# DisplayLCD-RS485.net
KiCad netlist of a schematic drawn in Altium Designer
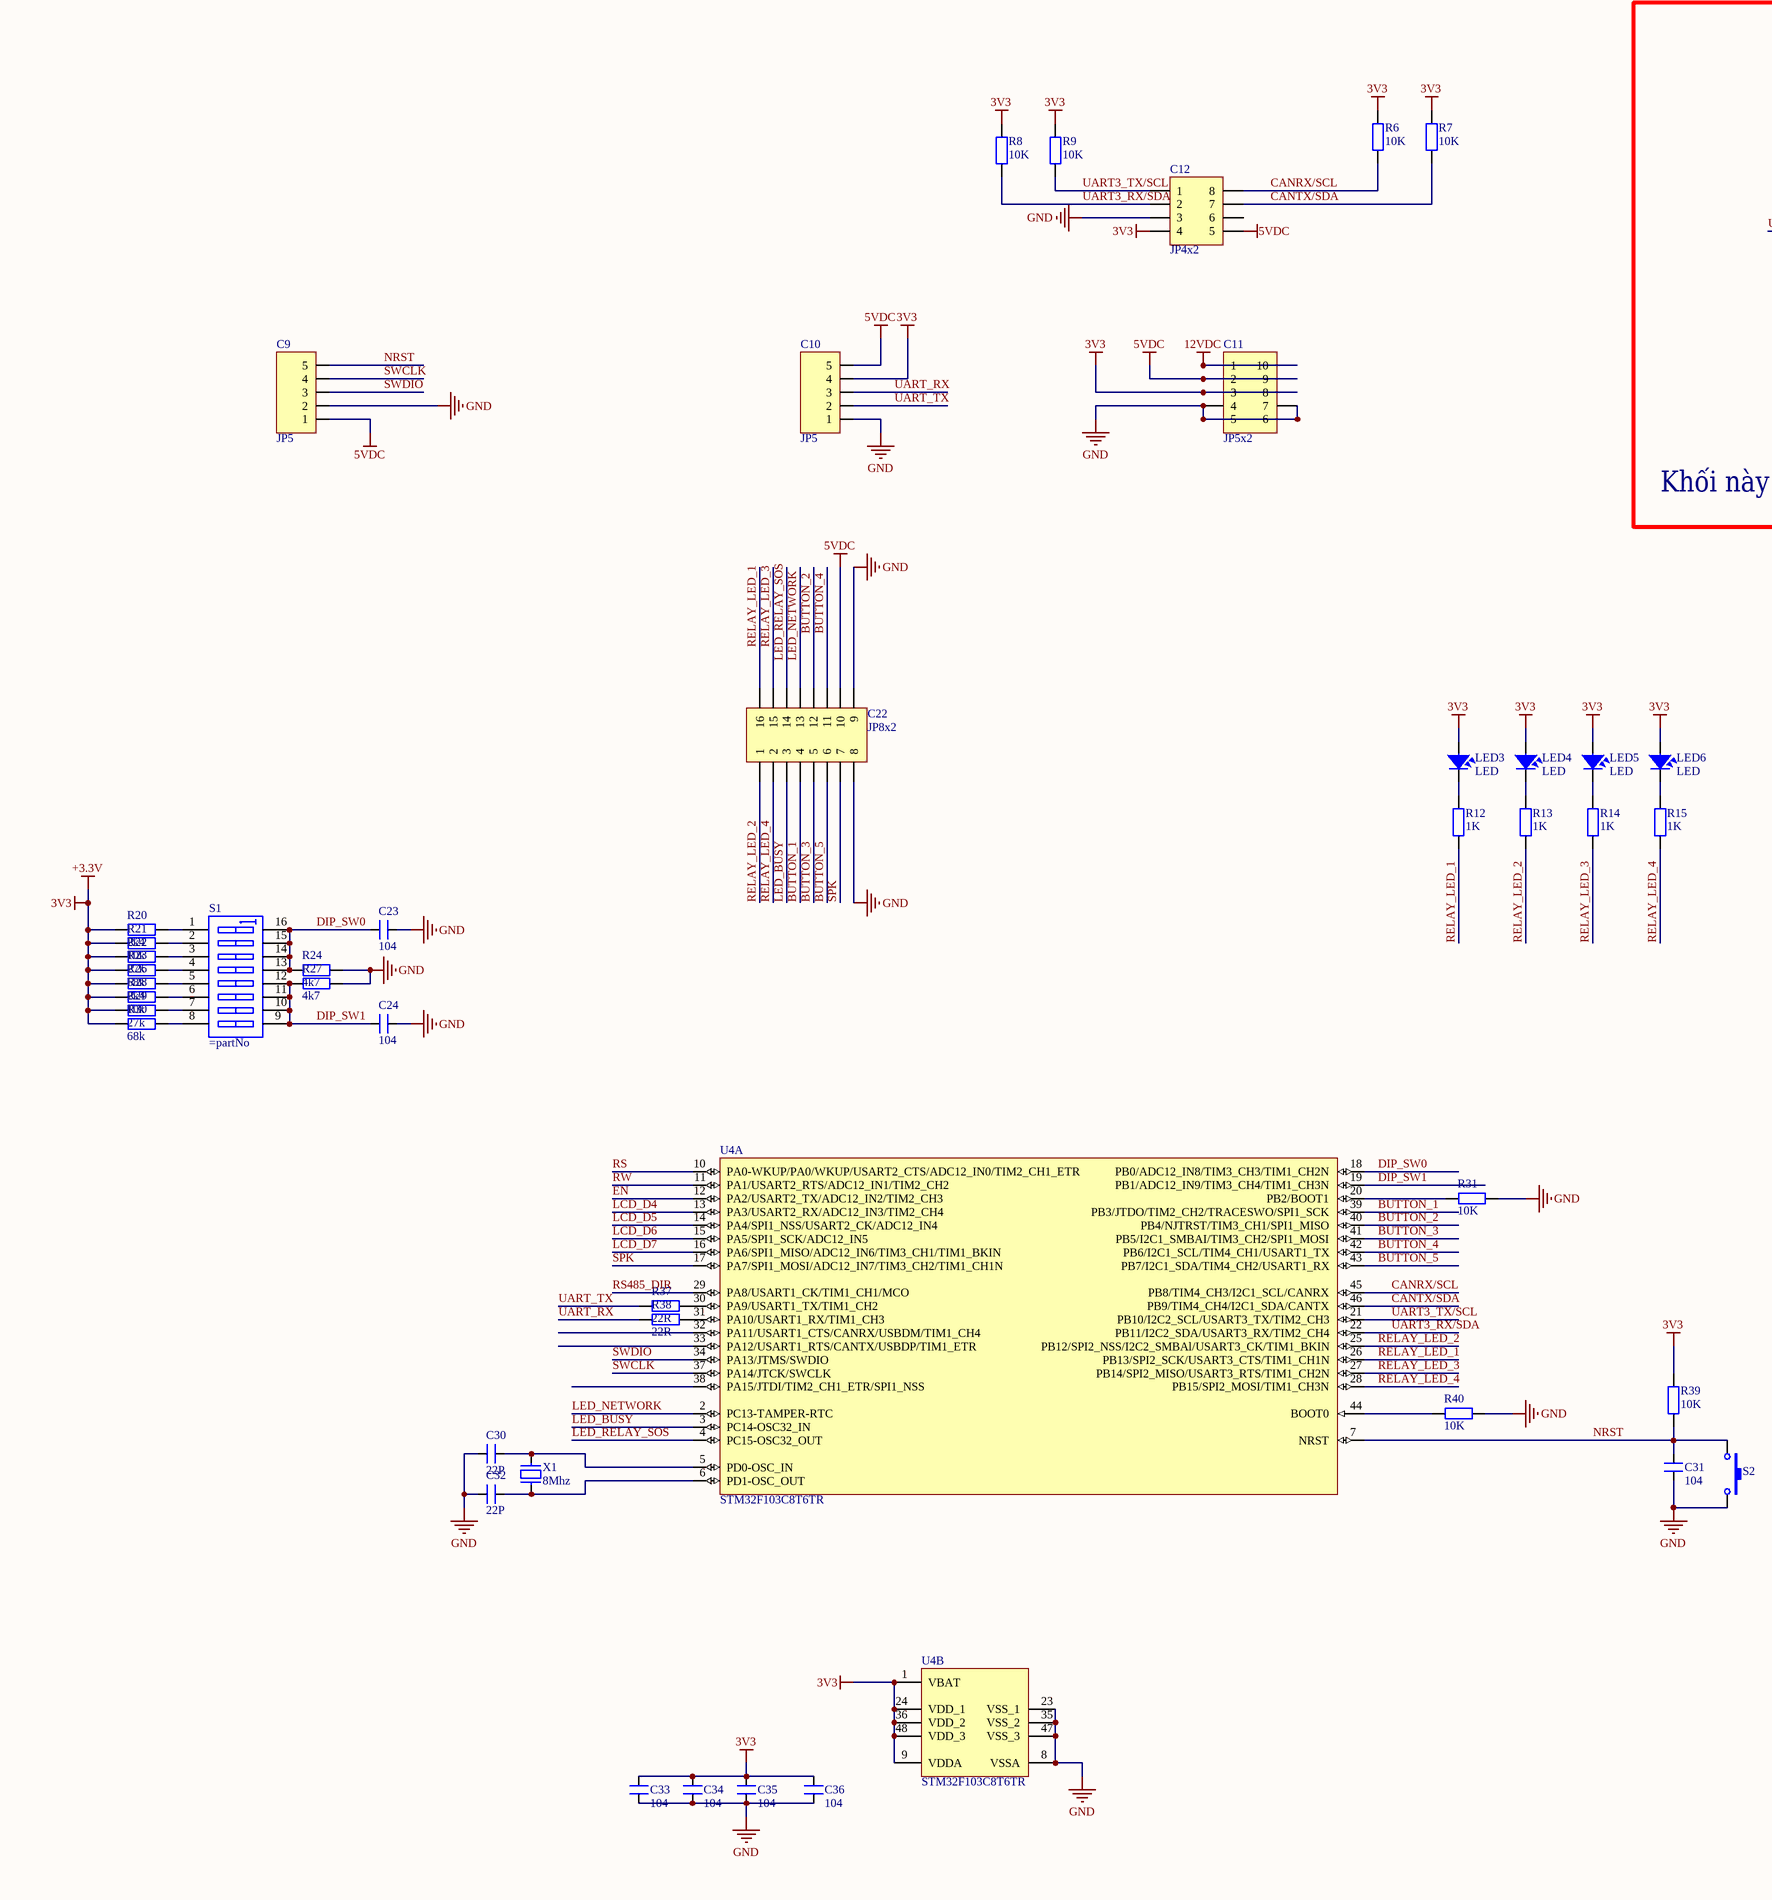
[diagram p0: DisplayLCD-RS485.SchDoc, left]
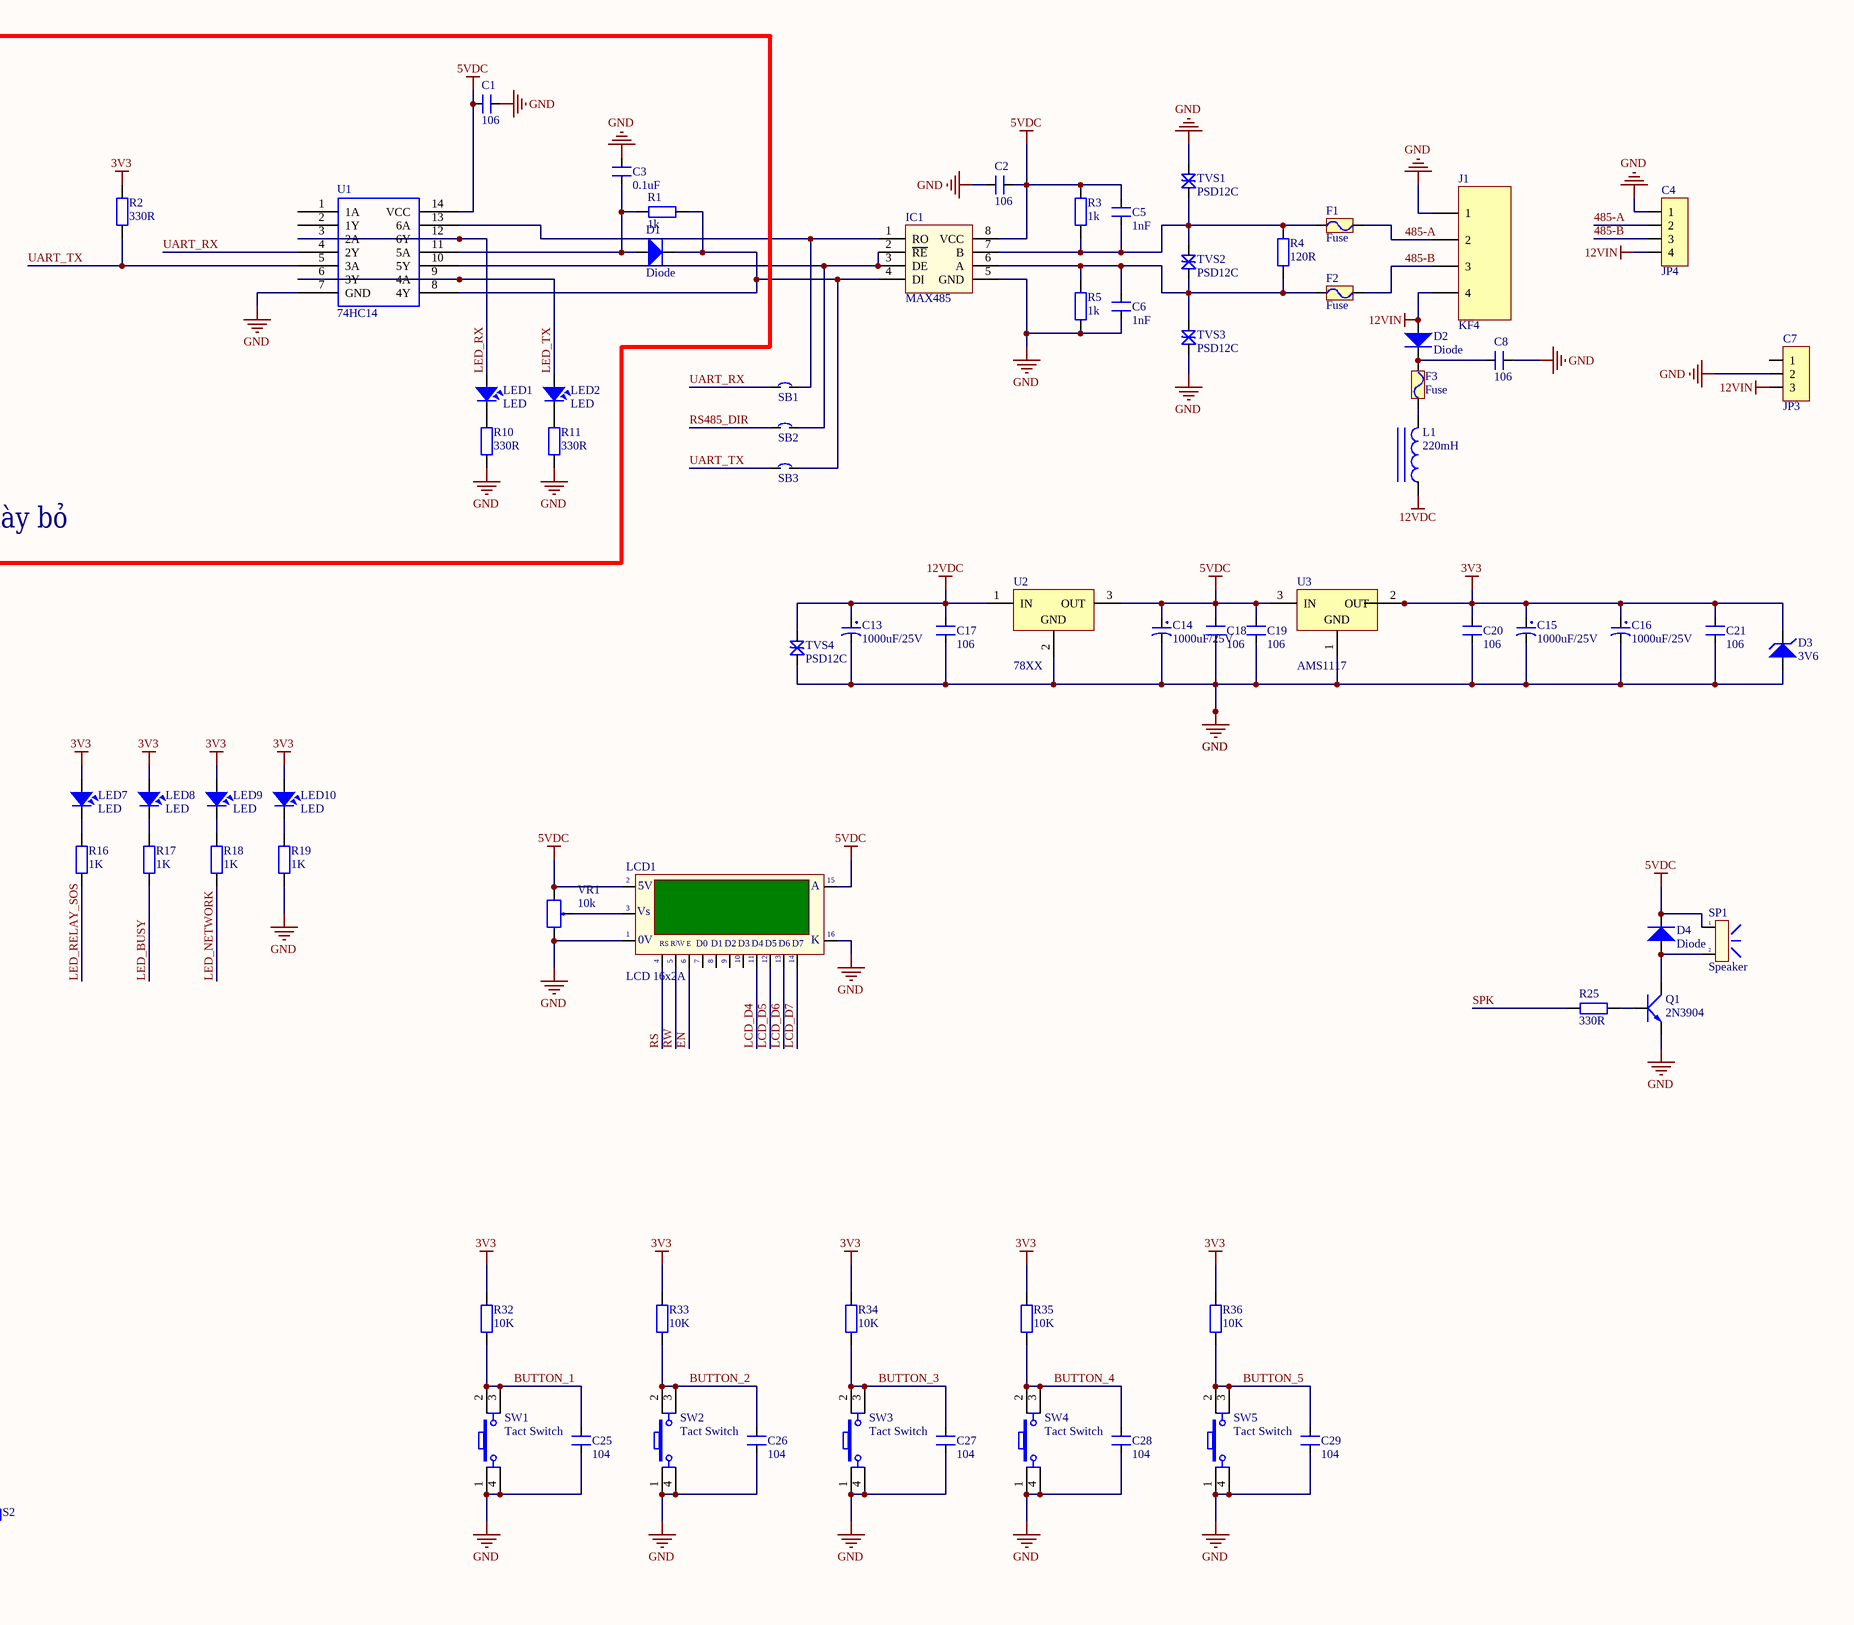
[diagram p1: DisplayLCD-RS485.SchDoc, right]

(export (version "E")
  (design (tool "Eeschema 10.0.6"))
  (components
    (comp (ref "C1")
      (value "106")
      (footprint "SM-0805")
      (description "Cap SMD")
      (libsource (lib "OBIT_TESLA") (part "CM"))
    )
    (comp (ref "C2")
      (value "106")
      (footprint "SM-0805")
      (description "Cap SMD")
      (libsource (lib "OBIT_TESLA") (part "CM"))
    )
    (comp (ref "C3")
      (value "0.1uF")
      (footprint "SM-0805")
      (description "Cap SMD")
      (libsource (lib "OBIT_TESLA") (part "CM"))
    )
    (comp (ref "C4")
      (value "JP4")
      (footprint "HDR2.54 4DV")
      (description "WR-PHD 2.54 mm Angled Socket Header")
      (fields
        (field (name "MANUFACTURER") "Würth Elektronik eiSos GmbH")
        (field (name "PARTNO") "613004143121")
        (field (name "CREATED BY") "Karrer Zheng")
      )
      (libsource (lib "OBIT_TESLA") (part "JP4"))
    )
    (comp (ref "C5")
      (value "1nF")
      (footprint "SM-0805")
      (description "Cap SMD")
      (libsource (lib "OBIT_TESLA") (part "CM"))
    )
    (comp (ref "C6")
      (value "1nF")
      (footprint "SM-0805")
      (description "Cap SMD")
      (libsource (lib "OBIT_TESLA") (part "CM"))
    )
    (comp (ref "C7")
      (value "JP3")
      (footprint "HDR2.54 3DV")
      (description "WR-PHD 2.54 mm Angled Socket Header")
      (fields
        (field (name "MANUFACTURER") "Würth Elektronik eiSos GmbH")
        (field (name "PARTNO") "613003143121")
        (field (name "CREATED BY") "Karrer Zheng")
      )
      (libsource (lib "OBIT_TESLA") (part "JP3"))
    )
    (comp (ref "C8")
      (value "106")
      (footprint "SM-0805")
      (description "Cap SMD")
      (libsource (lib "OBIT_TESLA") (part "CM"))
    )
    (comp (ref "C9")
      (value "JP5")
      (footprint "JP5-C1T")
      (description "WR-PHD 2.54 mm Angled Socket Header")
      (fields
        (field (name "MANUFACTURER") "Würth Elektronik eiSos GmbH")
        (field (name "PARTNO") "613005143121")
        (field (name "CREATED BY") "Karrer Zheng")
      )
      (libsource (lib "OBIT_TESLA") (part "JP5"))
    )
    (comp (ref "C10")
      (value "JP5")
      (footprint "HDR2.54 5DV")
      (description "WR-PHD 2.54 mm Angled Socket Header")
      (fields
        (field (name "MANUFACTURER") "Würth Elektronik eiSos GmbH")
        (field (name "PARTNO") "613005143121")
        (field (name "CREATED BY") "Karrer Zheng")
      )
      (libsource (lib "OBIT_TESLA") (part "JP5"))
    )
    (comp (ref "C11")
      (value "JP5x2")
      (footprint "JP5-D2T")
      (description "WR-PHD 2.54 mm Dual Socket Header")
      (fields
        (field (name "MANUFACTURER") "Würth Elektronik eiSos GmbH")
        (field (name "PARTNO") "61301021821")
        (field (name "CREATED BY") "Karrer Zheng")
      )
      (libsource (lib "OBIT_TESLA") (part "JP5x2"))
    )
    (comp (ref "C12")
      (value "JP4x2")
      (footprint "JP4-D2T")
      (description "WR-PHD 2.54 mm Dual Socket Header")
      (fields
        (field (name "MANUFACTURER") "Würth Elektronik eiSos GmbH")
        (field (name "PARTNO") "61300821821")
        (field (name "CREATED BY") "Karrer Zheng")
      )
      (libsource (lib "OBIT_TESLA") (part "JP4x2"))
    )
    (comp (ref "C13")
      (value "1000uF/25V")
      (footprint "CP1.5/3.4")
      (description "Cap 1000uF/16V - 220uF/50V")
      (libsource (lib "OBIT_TESLA") (part "CP4"))
    )
    (comp (ref "C14")
      (value "1000uF/25V")
      (footprint "CP1.5/3.4")
      (description "Cap 1000uF/16V - 220uF/50V")
      (libsource (lib "OBIT_TESLA") (part "CP4"))
    )
    (comp (ref "C15")
      (value "1000uF/25V")
      (footprint "CP1.5/3.4")
      (description "Cap 1000uF/16V - 220uF/50V")
      (libsource (lib "OBIT_TESLA") (part "CP4"))
    )
    (comp (ref "C16")
      (value "1000uF/25V")
      (footprint "CP1.5/3.4")
      (description "Cap 1000uF/16V - 220uF/50V")
      (libsource (lib "OBIT_TESLA") (part "CP4"))
    )
    (comp (ref "C17")
      (value "106")
      (footprint "SM-0805")
      (description "Cap SMD")
      (libsource (lib "OBIT_TESLA") (part "CM"))
    )
    (comp (ref "C18")
      (value "106")
      (footprint "SM-0805")
      (description "Cap SMD")
      (libsource (lib "OBIT_TESLA") (part "CM"))
    )
    (comp (ref "C19")
      (value "106")
      (footprint "SM-0805")
      (description "Cap SMD")
      (libsource (lib "OBIT_TESLA") (part "CM"))
    )
    (comp (ref "C20")
      (value "106")
      (footprint "SM-0805")
      (description "Cap SMD")
      (libsource (lib "OBIT_TESLA") (part "CM"))
    )
    (comp (ref "C21")
      (value "106")
      (footprint "SM-0805")
      (description "Cap SMD")
      (libsource (lib "OBIT_TESLA") (part "CM"))
    )
    (comp (ref "C22")
      (value "JP8x2")
      (footprint "61201621621")
      (description "WR-PHD 2.54 mm Dual Socket Header")
      (fields
        (field (name "MANUFACTURER") "Würth Elektronik eiSos GmbH")
        (field (name "PARTNO") "61301621821")
        (field (name "CREATED BY") "Karrer Zheng")
      )
      (libsource (lib "OBIT_TESLA") (part "JP8x2"))
    )
    (comp (ref "C23")
      (value "104")
      (footprint "SM-0805")
      (description "Cap SMD")
      (libsource (lib "OBIT_TESLA") (part "CM"))
    )
    (comp (ref "C24")
      (value "104")
      (footprint "SM-0805")
      (description "Cap SMD")
      (libsource (lib "OBIT_TESLA") (part "CM"))
    )
    (comp (ref "C25")
      (value "104")
      (footprint "SM-0805")
      (description "Cap SMD")
      (libsource (lib "OBIT_TESLA") (part "CM"))
    )
    (comp (ref "C26")
      (value "104")
      (footprint "SM-0805")
      (description "Cap SMD")
      (libsource (lib "OBIT_TESLA") (part "CM"))
    )
    (comp (ref "C27")
      (value "104")
      (footprint "SM-0805")
      (description "Cap SMD")
      (libsource (lib "OBIT_TESLA") (part "CM"))
    )
    (comp (ref "C28")
      (value "104")
      (footprint "SM-0805")
      (description "Cap SMD")
      (libsource (lib "OBIT_TESLA") (part "CM"))
    )
    (comp (ref "C29")
      (value "104")
      (footprint "SM-0805")
      (description "Cap SMD")
      (libsource (lib "OBIT_TESLA") (part "CM"))
    )
    (comp (ref "C30")
      (value "22P")
      (footprint "SM-0805")
      (description "Cap SMD")
      (libsource (lib "OBIT_TESLA") (part "CM"))
    )
    (comp (ref "C31")
      (value "104")
      (footprint "SM-0805")
      (description "Cap SMD")
      (libsource (lib "OBIT_TESLA") (part "CM"))
    )
    (comp (ref "C32")
      (value "22P")
      (footprint "SM-0805")
      (description "Cap SMD")
      (libsource (lib "OBIT_TESLA") (part "CM"))
    )
    (comp (ref "C33")
      (value "104")
      (footprint "SM-0805")
      (description "Cap SMD")
      (libsource (lib "OBIT_TESLA") (part "CM"))
    )
    (comp (ref "C34")
      (value "104")
      (footprint "SM-0805")
      (description "Cap SMD")
      (libsource (lib "OBIT_TESLA") (part "CM"))
    )
    (comp (ref "C35")
      (value "104")
      (footprint "SM-0805")
      (description "Cap SMD")
      (libsource (lib "OBIT_TESLA") (part "CM"))
    )
    (comp (ref "C36")
      (value "104")
      (footprint "SM-0805")
      (description "Cap SMD")
      (libsource (lib "OBIT_TESLA") (part "CM"))
    )
    (comp (ref "D1") (value "Diode") (footprint "DIO-SMD-106") (libsource (lib "OBIT_TESLA") (part "Diode")))
    (comp (ref "D2") (value "Diode") (footprint "DIO-SMD-106") (libsource (lib "OBIT_TESLA") (part "Diode")))
    (comp (ref "D3")
      (value "3V6")
      (footprint "SOD123")
      (description "Diode Zener")
      (fields (field (name "PART NUMBER") "BZV55-C5V1"))
      (libsource (lib "OBIT_TESLA") (part "Diode Zener"))
    )
    (comp (ref "D4") (value "Diode") (footprint "DIO-SMD-106") (libsource (lib "OBIT_TESLA") (part "Diode")))
    (comp (ref "F1") (value "Fuse") (footprint "RES-SMD-1812") (libsource (lib "OBIT_TESLA") (part "FUSE")))
    (comp (ref "F2") (value "Fuse") (footprint "RES-SMD-1812") (libsource (lib "OBIT_TESLA") (part "FUSE")))
    (comp (ref "F3") (value "Fuse") (footprint "RES-SMD-1812") (libsource (lib "") (part "FUSE_1")))
    (comp (ref "IC1")
      (value "MAX485")
      (footprint "SO8")
      (description "RS232 - RS485 (Same sn75176)")
      (libsource (lib "OBIT_TESLA") (part "MAX485"))
    )
    (comp (ref "J1")
      (value "KF4")
      (footprint "KF4-5.08")
      (fields
        (field (name "MANUFACTURER") "Würth Elektronik eiSos GmbH")
        (field (name "PARTNO") "691133710004")
        (field (name "CREATED BY") "Baojun Chen")
      )
      (libsource (lib "OBIT_TESLA") (part "KF4"))
    )
    (comp (ref "L1")
      (value "220mH")
      (footprint "INDUCTOR 3A VERTICAL")
      (description "Magnetic-Core Inductor")
      (libsource (lib "Tesla_Thinh") (part "Inductor Iron"))
    )
    (comp (ref "LCD1")
      (value "LCD 16x2A")
      (footprint "LCD16X2")
      (description "LCD dipslay 16 char, 2 line")
      (libsource (lib "OBIT_TESLA") (part "LCD16x2A"))
    )
    (comp (ref "LED1")
      (value "LED")
      (footprint "SM-LED-0805-Green")
      (libsource (lib "OBIT_TESLA") (part "LED"))
    )
    (comp (ref "LED2")
      (value "LED")
      (footprint "SM-LED-0805-Blue")
      (libsource (lib "OBIT_TESLA") (part "LED"))
    )
    (comp (ref "LED3") (value "LED") (footprint "LED-5-BLUE") (libsource (lib "OBIT_TESLA") (part "LED")))
    (comp (ref "LED4") (value "LED") (footprint "LED-5-BLUE") (libsource (lib "OBIT_TESLA") (part "LED")))
    (comp (ref "LED5") (value "LED") (footprint "LED-5-BLUE") (libsource (lib "OBIT_TESLA") (part "LED")))
    (comp (ref "LED6") (value "LED") (footprint "LED-5-BLUE") (libsource (lib "OBIT_TESLA") (part "LED")))
    (comp (ref "LED7") (value "LED") (footprint "LED-5-BLUE") (libsource (lib "OBIT_TESLA") (part "LED")))
    (comp (ref "LED8") (value "LED") (footprint "LED-5-BLUE") (libsource (lib "OBIT_TESLA") (part "LED")))
    (comp (ref "LED9") (value "LED") (footprint "LED-5-BLUE") (libsource (lib "OBIT_TESLA") (part "LED")))
    (comp (ref "LED10") (value "LED") (footprint "LED-5-BLUE") (libsource (lib "OBIT_TESLA") (part "LED")))
    (comp (ref "Q1")
      (value "2N3904")
      (footprint "SOT23-231")
      (description "NPN 600mW, ECB")
      (libsource (lib "OBIT_TESLA") (part "2N3904"))
    )
    (comp (ref "R1")
      (value "1k")
      (footprint "RES-SMD-0805")
      (description "Resistor R1/4W")
      (libsource (lib "OBIT_TESLA") (part "R"))
    )
    (comp (ref "R2")
      (value "330R")
      (footprint "RES-SMD-0805")
      (description "Resistor R1/4W")
      (libsource (lib "OBIT_TESLA") (part "R"))
    )
    (comp (ref "R3")
      (value "1k")
      (footprint "RES-SMD-0805")
      (description "Resistor R1/4W")
      (libsource (lib "OBIT_TESLA") (part "R"))
    )
    (comp (ref "R4")
      (value "120R")
      (footprint "RES-SMD-0805")
      (description "Resistor R1/4W")
      (libsource (lib "OBIT_TESLA") (part "R"))
    )
    (comp (ref "R5")
      (value "1k")
      (footprint "RES-SMD-0805")
      (description "Resistor R1/4W")
      (libsource (lib "OBIT_TESLA") (part "R"))
    )
    (comp (ref "R6")
      (value "10K")
      (footprint "RES-SMD-0805")
      (description "Resistor R1/4W")
      (libsource (lib "OBIT_TESLA") (part "R"))
    )
    (comp (ref "R7")
      (value "10K")
      (footprint "RES-SMD-0805")
      (description "Resistor R1/4W")
      (libsource (lib "OBIT_TESLA") (part "R"))
    )
    (comp (ref "R8")
      (value "10K")
      (footprint "RES-SMD-0805")
      (description "Resistor R1/4W")
      (libsource (lib "OBIT_TESLA") (part "R"))
    )
    (comp (ref "R9")
      (value "10K")
      (footprint "RES-SMD-0805")
      (description "Resistor R1/4W")
      (libsource (lib "OBIT_TESLA") (part "R"))
    )
    (comp (ref "R10")
      (value "330R")
      (footprint "RES-SMD-0805")
      (description "Resistor R1/4W")
      (libsource (lib "OBIT_TESLA") (part "R"))
    )
    (comp (ref "R11")
      (value "330R")
      (footprint "RES-SMD-0805")
      (description "Resistor R1/4W")
      (libsource (lib "OBIT_TESLA") (part "R"))
    )
    (comp (ref "R12")
      (value "1K")
      (footprint "RES-SMD-0805")
      (description "Resistor R1/4W")
      (libsource (lib "OBIT_TESLA") (part "R"))
    )
    (comp (ref "R13")
      (value "1K")
      (footprint "RES-SMD-0805")
      (description "Resistor R1/4W")
      (libsource (lib "OBIT_TESLA") (part "R"))
    )
    (comp (ref "R14")
      (value "1K")
      (footprint "RES-SMD-0805")
      (description "Resistor R1/4W")
      (libsource (lib "OBIT_TESLA") (part "R"))
    )
    (comp (ref "R15")
      (value "1K")
      (footprint "RES-SMD-0805")
      (description "Resistor R1/4W")
      (libsource (lib "OBIT_TESLA") (part "R"))
    )
    (comp (ref "R16")
      (value "1K")
      (footprint "RES-SMD-0805")
      (description "Resistor R1/4W")
      (libsource (lib "OBIT_TESLA") (part "R"))
    )
    (comp (ref "R17")
      (value "1K")
      (footprint "RES-SMD-0805")
      (description "Resistor R1/4W")
      (libsource (lib "OBIT_TESLA") (part "R"))
    )
    (comp (ref "R18")
      (value "1K")
      (footprint "RES-SMD-0805")
      (description "Resistor R1/4W")
      (libsource (lib "OBIT_TESLA") (part "R"))
    )
    (comp (ref "R19")
      (value "1K")
      (footprint "RES-SMD-0805")
      (description "Resistor R1/4W")
      (libsource (lib "OBIT_TESLA") (part "R"))
    )
    (comp (ref "R20")
      (value "2k4")
      (footprint "RES-SMD-0805")
      (description "Resistor R1/4W")
      (libsource (lib "OBIT_TESLA") (part "R"))
    )
    (comp (ref "R21")
      (value "10k")
      (footprint "RES-SMD-0805")
      (description "Resistor R1/4W")
      (libsource (lib "OBIT_TESLA") (part "R"))
    )
    (comp (ref "R22")
      (value "27k")
      (footprint "RES-SMD-0805")
      (description "Resistor R1/4W")
      (libsource (lib "OBIT_TESLA") (part "R"))
    )
    (comp (ref "R23")
      (value "68k")
      (footprint "RES-SMD-0805")
      (description "Resistor R1/4W")
      (libsource (lib "OBIT_TESLA") (part "R"))
    )
    (comp (ref "R24")
      (value "4k7")
      (footprint "RES-SMD-0805")
      (description "Resistor R1/4W")
      (libsource (lib "OBIT_TESLA") (part "R"))
    )
    (comp (ref "R25")
      (value "330R")
      (footprint "RES-SMD-0805")
      (description "Resistor R1/4W")
      (libsource (lib "OBIT_TESLA") (part "R"))
    )
    (comp (ref "R26")
      (value "2k4")
      (footprint "RES-SMD-0805")
      (description "Resistor R1/4W")
      (libsource (lib "OBIT_TESLA") (part "R"))
    )
    (comp (ref "R27")
      (value "4k7")
      (footprint "RES-SMD-0805")
      (description "Resistor R1/4W")
      (libsource (lib "OBIT_TESLA") (part "R"))
    )
    (comp (ref "R28")
      (value "10k")
      (footprint "RES-SMD-0805")
      (description "Resistor R1/4W")
      (libsource (lib "OBIT_TESLA") (part "R"))
    )
    (comp (ref "R29")
      (value "27k")
      (footprint "RES-SMD-0805")
      (description "Resistor R1/4W")
      (libsource (lib "OBIT_TESLA") (part "R"))
    )
    (comp (ref "R30")
      (value "68k")
      (footprint "RES-SMD-0805")
      (description "Resistor R1/4W")
      (libsource (lib "OBIT_TESLA") (part "R"))
    )
    (comp (ref "R31")
      (value "10K")
      (footprint "RES-SMD-0805")
      (description "Resistor R1/4W")
      (libsource (lib "OBIT_TESLA") (part "R"))
    )
    (comp (ref "R32")
      (value "10K")
      (footprint "RES-SMD-0805")
      (description "Resistor R1/4W")
      (libsource (lib "OBIT_TESLA") (part "R"))
    )
    (comp (ref "R33")
      (value "10K")
      (footprint "RES-SMD-0805")
      (description "Resistor R1/4W")
      (libsource (lib "OBIT_TESLA") (part "R"))
    )
    (comp (ref "R34")
      (value "10K")
      (footprint "RES-SMD-0805")
      (description "Resistor R1/4W")
      (libsource (lib "OBIT_TESLA") (part "R"))
    )
    (comp (ref "R35")
      (value "10K")
      (footprint "RES-SMD-0805")
      (description "Resistor R1/4W")
      (libsource (lib "OBIT_TESLA") (part "R"))
    )
    (comp (ref "R36")
      (value "10K")
      (footprint "RES-SMD-0805")
      (description "Resistor R1/4W")
      (libsource (lib "OBIT_TESLA") (part "R"))
    )
    (comp (ref "R37")
      (value "22R")
      (footprint "RES-SMD-0805")
      (description "Resistor R1/4W")
      (libsource (lib "OBIT_TESLA") (part "R"))
    )
    (comp (ref "R38")
      (value "22R")
      (footprint "RES-SMD-0805")
      (description "Resistor R1/4W")
      (libsource (lib "OBIT_TESLA") (part "R"))
    )
    (comp (ref "R39")
      (value "10K")
      (footprint "RES-SMD-0805")
      (description "Resistor R1/4W")
      (libsource (lib "OBIT_TESLA") (part "R"))
    )
    (comp (ref "R40")
      (value "10K")
      (footprint "RES-SMD-0805")
      (description "Resistor R1/4W")
      (libsource (lib "OBIT_TESLA") (part "R"))
    )
    (comp (ref "S1")
      (value "~")
      (footprint "SW-DIP8")
      (description "WS-DITV 2.54 mm small compact THT flat actuator with top tape")
      (fields
        (field (name "MANUFACTURER") "Wurth Elektronik")
        (field (name "PART NO.") "418127160908")
        (field (name "CREATED BY") "Baojun Chen")
      )
      (libsource (lib "OBIT_TESLA") (part "SWDIP8"))
    )
    (comp (ref "S2")
      (value "SW")
      (footprint "BUTTON-SMD 2PIN")
      (description "Switch-Button")
      (fields (field (name "PUBLISHER") "Altium Limited"))
      (libsource (lib "OBIT_TESLA") (part "SW-Button"))
    )
    (comp (ref "SB1") (value "SB") (footprint "SB") (libsource (lib "OBIT_TESLA") (part "SB")))
    (comp (ref "SB2") (value "SB") (footprint "SB") (libsource (lib "OBIT_TESLA") (part "SB")))
    (comp (ref "SB3") (value "SB") (footprint "SB") (libsource (lib "OBIT_TESLA") (part "SB")))
    (comp (ref "SP1")
      (value "Speaker")
      (footprint "SPK")
      (description "Speaker Chip")
      (libsource (lib "OBIT_TESLA") (part "SPK"))
    )
    (comp (ref "SW1")
      (value "Tact Switch")
      (footprint "SW4_12X12_LAGER")
      (libsource (lib "OBIT_TESLA") (part "SW4"))
    )
    (comp (ref "SW2")
      (value "Tact Switch")
      (footprint "SW4_12X12_LAGER")
      (libsource (lib "OBIT_TESLA") (part "SW4"))
    )
    (comp (ref "SW3")
      (value "Tact Switch")
      (footprint "SW4_12X12_LAGER")
      (libsource (lib "OBIT_TESLA") (part "SW4"))
    )
    (comp (ref "SW4")
      (value "Tact Switch")
      (footprint "SW4_12X12_LAGER")
      (libsource (lib "OBIT_TESLA") (part "SW4"))
    )
    (comp (ref "SW5")
      (value "Tact Switch")
      (footprint "SW4_12X12_LAGER")
      (libsource (lib "OBIT_TESLA") (part "SW4"))
    )
    (comp (ref "TVS1")
      (value "PSD12C")
      (footprint "DIO-SMD-B")
      (libsource (lib "OBIT_TESLA") (part "Diode TVS"))
    )
    (comp (ref "TVS2")
      (value "PSD12C")
      (footprint "DIO-SMD-B")
      (libsource (lib "OBIT_TESLA") (part "Diode TVS"))
    )
    (comp (ref "TVS3")
      (value "PSD12C")
      (footprint "DIO-SMD-B")
      (libsource (lib "OBIT_TESLA") (part "Diode TVS"))
    )
    (comp (ref "TVS4")
      (value "PSD12C")
      (footprint "DIO-SMD-B")
      (libsource (lib "OBIT_TESLA") (part "Diode TVS"))
    )
    (comp (ref "U1") (value "74HC14") (footprint "SO14") (libsource (lib "OBIT_TESLA") (part "74HC14")))
    (comp (ref "U2") (value "78XX") (footprint "TO252-123") (libsource (lib "OBIT_TESLA") (part "LM78XX")))
    (comp (ref "U3") (value "AMS1117") (footprint "SOT223") (libsource (lib "OBIT_TESLA") (part "AMS117")))
    (comp (ref "U4")
      (value "STM32F103C8T6TR")
      (footprint "STM-LQFP48_N")
      (libsource (lib "OBIT_TESLA") (part "STM32F103C8T6TR"))
    )
    (comp (ref "VR1") (value "10k") (footprint "VR-S2") (libsource (lib "OBIT_TESLA") (part "Resistor Var")))
    (comp (ref "X1")
      (value "8Mhz")
      (footprint "XT2")
      (description "Crystal, 32.768 KHz, -40 to 85 degC, 3.2 x 1.5 x 0.9 mm SMD")
      (libsource (lib "OBIT_TESLA") (part "XT2"))
    )
  )
  (nets
    (net (code "1") (name "+3.3V") (class "Default")
      (node (ref "C10") (pin "4") (pinfunction "4_4") (pintype "passive"))
      (node (ref "C11") (pin "3") (pinfunction "3_3") (pintype "passive"))
      (node (ref "C11") (pin "8") (pinfunction "8_8") (pintype "passive"))
      (node (ref "C12") (pin "4") (pinfunction "4_4") (pintype "passive"))
      (node (ref "C15") (pin "1") (pinfunction "1_1") (pintype "passive"))
      (node (ref "C16") (pin "1") (pinfunction "1_1") (pintype "passive"))
      (node (ref "C20") (pin "1") (pinfunction "1_1") (pintype "passive"))
      (node (ref "C21") (pin "1") (pinfunction "1_1") (pintype "passive"))
      (node (ref "C33") (pin "1") (pinfunction "1_1") (pintype "passive"))
      (node (ref "C34") (pin "1") (pinfunction "1_1") (pintype "passive"))
      (node (ref "C35") (pin "1") (pinfunction "1_1") (pintype "passive"))
      (node (ref "C36") (pin "1") (pinfunction "1_1") (pintype "passive"))
      (node (ref "D3") (pin "2") (pinfunction "2_2") (pintype "passive"))
      (node (ref "LED10") (pin "1") (pinfunction "1_1") (pintype "passive"))
      (node (ref "LED3") (pin "1") (pinfunction "1_1") (pintype "passive"))
      (node (ref "LED4") (pin "1") (pinfunction "1_1") (pintype "passive"))
      (node (ref "LED5") (pin "1") (pinfunction "1_1") (pintype "passive"))
      (node (ref "LED6") (pin "1") (pinfunction "1_1") (pintype "passive"))
      (node (ref "LED7") (pin "1") (pinfunction "1_1") (pintype "passive"))
      (node (ref "LED8") (pin "1") (pinfunction "1_1") (pintype "passive"))
      (node (ref "LED9") (pin "1") (pinfunction "1_1") (pintype "passive"))
      (node (ref "R2") (pin "1") (pinfunction "1_1") (pintype "passive"))
      (node (ref "R20") (pin "2") (pinfunction "2_2") (pintype "passive"))
      (node (ref "R21") (pin "2") (pinfunction "2_2") (pintype "passive"))
      (node (ref "R22") (pin "2") (pinfunction "2_2") (pintype "passive"))
      (node (ref "R23") (pin "2") (pinfunction "2_2") (pintype "passive"))
      (node (ref "R26") (pin "2") (pinfunction "2_2") (pintype "passive"))
      (node (ref "R28") (pin "2") (pinfunction "2_2") (pintype "passive"))
      (node (ref "R29") (pin "2") (pinfunction "2_2") (pintype "passive"))
      (node (ref "R30") (pin "2") (pinfunction "2_2") (pintype "passive"))
      (node (ref "R32") (pin "1") (pinfunction "1_1") (pintype "passive"))
      (node (ref "R33") (pin "1") (pinfunction "1_1") (pintype "passive"))
      (node (ref "R34") (pin "1") (pinfunction "1_1") (pintype "passive"))
      (node (ref "R35") (pin "1") (pinfunction "1_1") (pintype "passive"))
      (node (ref "R36") (pin "1") (pinfunction "1_1") (pintype "passive"))
      (node (ref "R39") (pin "1") (pinfunction "1_1") (pintype "passive"))
      (node (ref "R6") (pin "1") (pinfunction "1_1") (pintype "passive"))
      (node (ref "R7") (pin "1") (pinfunction "1_1") (pintype "passive"))
      (node (ref "R8") (pin "1") (pinfunction "1_1") (pintype "passive"))
      (node (ref "R9") (pin "1") (pinfunction "1_1") (pintype "passive"))
      (node (ref "U3") (pin "2") (pinfunction "OUT_2") (pintype "power_in"))
      (node (ref "U3") (pin "4") (pinfunction "4_4") (pintype "passive"))
      (node (ref "U4") (pin "1") (pinfunction "VBAT_1") (pintype "power_in"))
      (node (ref "U4") (pin "24") (pinfunction "VDD_1_24") (pintype "power_in"))
      (node (ref "U4") (pin "36") (pinfunction "VDD_2_36") (pintype "power_in"))
      (node (ref "U4") (pin "48") (pinfunction "VDD_3_48") (pintype "power_in"))
      (node (ref "U4") (pin "9") (pinfunction "VDDA_9") (pintype "power_in"))
    )
    (net (code "2") (name "/485-A") (class "Default")
      (node (ref "C4") (pin "2") (pinfunction "2_2") (pintype "passive"))
      (node (ref "F1") (pin "2") (pinfunction "2_2") (pintype "passive"))
      (node (ref "J1") (pin "2") (pinfunction "2_2") (pintype "passive"))
    )
    (net (code "3") (name "/485-B") (class "Default")
      (node (ref "C4") (pin "3") (pinfunction "3_3") (pintype "passive"))
      (node (ref "F2") (pin "2") (pinfunction "2_2") (pintype "passive"))
      (node (ref "J1") (pin "3") (pinfunction "3_3") (pintype "passive"))
    )
    (net (code "4") (name "/BUTTON_1") (class "Default")
      (node (ref "C22") (pin "4") (pinfunction "4_4") (pintype "passive"))
      (node (ref "C25") (pin "2") (pinfunction "2_2") (pintype "passive"))
      (node (ref "R32") (pin "2") (pinfunction "2_2") (pintype "passive"))
      (node (ref "SW1") (pin "2") (pintype "passive"))
      (node (ref "SW1") (pin "3") (pintype "passive"))
      (node (ref "U4") (pin "39") (pinfunction "PB3/JTDO/TIM2_CH2/TRACESWO/SPI1_SCK_39") (pintype "bidirectional"))
    )
    (net (code "5") (name "/BUTTON_2") (class "Default")
      (node (ref "C22") (pin "12") (pinfunction "12_12") (pintype "passive"))
      (node (ref "C26") (pin "2") (pinfunction "2_2") (pintype "passive"))
      (node (ref "R33") (pin "2") (pinfunction "2_2") (pintype "passive"))
      (node (ref "SW2") (pin "2") (pintype "passive"))
      (node (ref "SW2") (pin "3") (pintype "passive"))
      (node (ref "U4") (pin "40") (pinfunction "PB4/NJTRST/TIM3_CH1/SPI1_MISO_40") (pintype "bidirectional"))
    )
    (net (code "6") (name "/BUTTON_3") (class "Default")
      (node (ref "C22") (pin "5") (pinfunction "5_5") (pintype "passive"))
      (node (ref "C27") (pin "2") (pinfunction "2_2") (pintype "passive"))
      (node (ref "R34") (pin "2") (pinfunction "2_2") (pintype "passive"))
      (node (ref "SW3") (pin "2") (pintype "passive"))
      (node (ref "SW3") (pin "3") (pintype "passive"))
      (node (ref "U4") (pin "41") (pinfunction "PB5/I2C1_SMBAI/TIM3_CH2/SPI1_MOSI_41") (pintype "bidirectional"))
    )
    (net (code "7") (name "/BUTTON_4") (class "Default")
      (node (ref "C22") (pin "11") (pinfunction "11_11") (pintype "passive"))
      (node (ref "C28") (pin "2") (pinfunction "2_2") (pintype "passive"))
      (node (ref "R35") (pin "2") (pinfunction "2_2") (pintype "passive"))
      (node (ref "SW4") (pin "2") (pintype "passive"))
      (node (ref "SW4") (pin "3") (pintype "passive"))
      (node (ref "U4") (pin "42") (pinfunction "PB6/I2C1_SCL/TIM4_CH1/USART1_TX_42") (pintype "bidirectional"))
    )
    (net (code "8") (name "/BUTTON_5") (class "Default")
      (node (ref "C22") (pin "6") (pinfunction "6_6") (pintype "passive"))
      (node (ref "C29") (pin "2") (pinfunction "2_2") (pintype "passive"))
      (node (ref "R36") (pin "2") (pinfunction "2_2") (pintype "passive"))
      (node (ref "SW5") (pin "2") (pintype "passive"))
      (node (ref "SW5") (pin "3") (pintype "passive"))
      (node (ref "U4") (pin "43") (pinfunction "PB7/I2C1_SDA/TIM4_CH2/USART1_RX_43") (pintype "bidirectional"))
    )
    (net (code "9") (name "/CANRX{slash}SCL") (class "Default")
      (node (ref "C12") (pin "8") (pinfunction "8_8") (pintype "passive"))
      (node (ref "R6") (pin "2") (pinfunction "2_2") (pintype "passive"))
      (node (ref "U4") (pin "45") (pinfunction "PB8/TIM4_CH3/I2C1_SCL/CANRX_45") (pintype "bidirectional"))
    )
    (net (code "10") (name "/CANTX{slash}SDA") (class "Default")
      (node (ref "C12") (pin "7") (pinfunction "7_7") (pintype "passive"))
      (node (ref "R7") (pin "2") (pinfunction "2_2") (pintype "passive"))
      (node (ref "U4") (pin "46") (pinfunction "PB9/TIM4_CH4/I2C1_SDA/CANTX_46") (pintype "bidirectional"))
    )
    (net (code "11") (name "/DIP_SW0") (class "Default")
      (node (ref "C23") (pin "2") (pinfunction "2_2") (pintype "passive"))
      (node (ref "R24") (pin "2") (pinfunction "2_2") (pintype "passive"))
      (node (ref "S1") (pin "13") (pinfunction "13_13") (pintype "passive"))
      (node (ref "S1") (pin "14") (pinfunction "14_14") (pintype "passive"))
      (node (ref "S1") (pin "15") (pinfunction "15_15") (pintype "passive"))
      (node (ref "S1") (pin "16") (pinfunction "16_16") (pintype "passive"))
      (node (ref "U4") (pin "18") (pinfunction "PB0/ADC12_IN8/TIM3_CH3/TIM1_CH2N_18") (pintype "bidirectional"))
    )
    (net (code "12") (name "/DIP_SW1") (class "Default")
      (node (ref "C24") (pin "2") (pinfunction "2_2") (pintype "passive"))
      (node (ref "R27") (pin "2") (pinfunction "2_2") (pintype "passive"))
      (node (ref "S1") (pin "10") (pinfunction "10_10") (pintype "passive"))
      (node (ref "S1") (pin "11") (pinfunction "11_11") (pintype "passive"))
      (node (ref "S1") (pin "12") (pinfunction "12_12") (pintype "passive"))
      (node (ref "S1") (pin "9") (pinfunction "9_9") (pintype "passive"))
      (node (ref "U4") (pin "19") (pinfunction "PB1/ADC12_IN9/TIM3_CH4/TIM1_CH3N_19") (pintype "bidirectional"))
    )
    (net (code "13") (name "/EN") (class "Default")
      (node (ref "LCD1") (pin "6") (pinfunction "~{EN}_6") (pintype "passive"))
      (node (ref "U4") (pin "12") (pinfunction "PA2/USART2_TX/ADC12_IN2/TIM2_CH3_12") (pintype "bidirectional"))
    )
    (net (code "14") (name "/LCD_D4") (class "Default")
      (node (ref "LCD1") (pin "11") (pinfunction "D4_11") (pintype "passive"))
      (node (ref "U4") (pin "13") (pinfunction "PA3/USART2_RX/ADC12_IN3/TIM2_CH4_13") (pintype "bidirectional"))
    )
    (net (code "15") (name "/LCD_D5") (class "Default")
      (node (ref "LCD1") (pin "12") (pinfunction "D5_12") (pintype "passive"))
      (node (ref "U4") (pin "14") (pinfunction "PA4/SPI1_NSS/USART2_CK/ADC12_IN4_14") (pintype "bidirectional"))
    )
    (net (code "16") (name "/LCD_D6") (class "Default")
      (node (ref "LCD1") (pin "13") (pinfunction "D6_13") (pintype "passive"))
      (node (ref "U4") (pin "15") (pinfunction "PA5/SPI1_SCK/ADC12_IN5_15") (pintype "bidirectional"))
    )
    (net (code "17") (name "/LCD_D7") (class "Default")
      (node (ref "LCD1") (pin "14") (pinfunction "D7_14") (pintype "passive"))
      (node (ref "U4") (pin "16") (pinfunction "PA6/SPI1_MISO/ADC12_IN6/TIM3_CH1/TIM1_BKIN_16") (pintype "bidirectional"))
    )
    (net (code "18") (name "/LED_BUSY") (class "Default")
      (node (ref "C22") (pin "3") (pinfunction "3_3") (pintype "passive"))
      (node (ref "R17") (pin "2") (pinfunction "2_2") (pintype "passive"))
      (node (ref "U4") (pin "3") (pinfunction "PC14-OSC32_IN_3") (pintype "bidirectional"))
    )
    (net (code "19") (name "/LED_NETWORK") (class "Default")
      (node (ref "C22") (pin "13") (pinfunction "13_13") (pintype "passive"))
      (node (ref "R18") (pin "2") (pinfunction "2_2") (pintype "passive"))
      (node (ref "U4") (pin "2") (pinfunction "PC13-TAMPER-RTC_2") (pintype "bidirectional"))
    )
    (net (code "20") (name "/LED_RELAY_SOS") (class "Default")
      (node (ref "C22") (pin "14") (pinfunction "14_14") (pintype "passive"))
      (node (ref "R16") (pin "2") (pinfunction "2_2") (pintype "passive"))
      (node (ref "U4") (pin "4") (pinfunction "PC15-OSC32_OUT_4") (pintype "bidirectional"))
    )
    (net (code "21") (name "/LED_RX") (class "Default")
      (node (ref "LED1") (pin "1") (pinfunction "1_1") (pintype "passive"))
      (node (ref "U1") (pin "12") (pinfunction "6Y_12") (pintype "passive"))
      (node (ref "U1") (pin "3") (pinfunction "2A_3") (pintype "passive"))
    )
    (net (code "22") (name "/LED_TX") (class "Default")
      (node (ref "LED2") (pin "1") (pinfunction "1_1") (pintype "passive"))
      (node (ref "U1") (pin "6") (pinfunction "3Y_6") (pintype "passive"))
      (node (ref "U1") (pin "9") (pinfunction "4A_9") (pintype "passive"))
    )
    (net (code "23") (name "/NRST") (class "Default")
      (node (ref "C31") (pin "2") (pinfunction "2_2") (pintype "passive"))
      (node (ref "C9") (pin "5") (pinfunction "5_5") (pintype "passive"))
      (node (ref "R39") (pin "2") (pinfunction "2_2") (pintype "passive"))
      (node (ref "S2") (pin "1") (pinfunction "1_1") (pintype "passive"))
      (node (ref "U4") (pin "7") (pinfunction "NRST_7") (pintype "bidirectional"))
    )
    (net (code "24") (name "/RELAY_LED_1") (class "Default")
      (node (ref "C22") (pin "16") (pinfunction "16_16") (pintype "passive"))
      (node (ref "R12") (pin "2") (pinfunction "2_2") (pintype "passive"))
      (node (ref "U4") (pin "26") (pinfunction "PB13/SPI2_SCK/USART3_CTS/TIM1_CH1N_26") (pintype "bidirectional"))
    )
    (net (code "25") (name "/RELAY_LED_2") (class "Default")
      (node (ref "C22") (pin "1") (pinfunction "1_1") (pintype "passive"))
      (node (ref "R13") (pin "2") (pinfunction "2_2") (pintype "passive"))
      (node (ref "U4") (pin "25") (pinfunction "PB12/SPI2_NSS/I2C2_SMBAl/USART3_CK/TIM1_BKIN_25") (pintype "bidirectional"))
    )
    (net (code "26") (name "/RELAY_LED_3") (class "Default")
      (node (ref "C22") (pin "15") (pinfunction "15_15") (pintype "passive"))
      (node (ref "R14") (pin "2") (pinfunction "2_2") (pintype "passive"))
      (node (ref "U4") (pin "27") (pinfunction "PB14/SPI2_MISO/USART3_RTS/TIM1_CH2N_27") (pintype "bidirectional"))
    )
    (net (code "27") (name "/RELAY_LED_4") (class "Default")
      (node (ref "C22") (pin "2") (pinfunction "2_2") (pintype "passive"))
      (node (ref "R15") (pin "2") (pinfunction "2_2") (pintype "passive"))
      (node (ref "U4") (pin "28") (pinfunction "PB15/SPI2_MOSI/TIM1_CH3N_28") (pintype "bidirectional"))
    )
    (net (code "28") (name "/RS") (class "Default")
      (node (ref "LCD1") (pin "4") (pinfunction "RS_4") (pintype "passive"))
      (node (ref "U4") (pin "10") (pinfunction "PA0-WKUP/PA0/WKUP/USART2_CTS/ADC12_IN0/TIM2_CH1_ETR_10") (pintype "bidirectional"))
    )
    (net (code "29") (name "/RS485_DIR") (class "Default")
      (node (ref "SB2") (pin "1") (pintype "passive"))
      (node (ref "U4") (pin "29") (pinfunction "PA8/USART1_CK/TIM1_CH1/MCO_29") (pintype "bidirectional"))
    )
    (net (code "30") (name "/RW") (class "Default")
      (node (ref "LCD1") (pin "5") (pinfunction "R/~{W}_5") (pintype "passive"))
      (node (ref "U4") (pin "11") (pinfunction "PA1/USART2_RTS/ADC12_IN1/TIM2_CH2_11") (pintype "bidirectional"))
    )
    (net (code "31") (name "/SPK") (class "Default")
      (node (ref "C22") (pin "7") (pinfunction "7_7") (pintype "passive"))
      (node (ref "R25") (pin "1") (pinfunction "1_1") (pintype "passive"))
      (node (ref "U4") (pin "17") (pinfunction "PA7/SPI1_MOSI/ADC12_IN7/TIM3_CH2/TIM1_CH1N_17") (pintype "bidirectional"))
    )
    (net (code "32") (name "/SWCLK") (class "Default")
      (node (ref "C9") (pin "4") (pinfunction "4_4") (pintype "passive"))
      (node (ref "U4") (pin "37") (pinfunction "PA14/JTCK/SWCLK_37") (pintype "bidirectional"))
    )
    (net (code "33") (name "/SWDIO") (class "Default")
      (node (ref "C9") (pin "3") (pinfunction "3_3") (pintype "passive"))
      (node (ref "U4") (pin "34") (pinfunction "PA13/JTMS/SWDIO_34") (pintype "bidirectional"))
    )
    (net (code "34") (name "/UART3_RX{slash}SDA") (class "Default")
      (node (ref "C12") (pin "2") (pinfunction "2_2") (pintype "passive"))
      (node (ref "R8") (pin "2") (pinfunction "2_2") (pintype "passive"))
      (node (ref "U4") (pin "22") (pinfunction "PB11/I2C2_SDA/USART3_RX/TIM2_CH4_22") (pintype "bidirectional"))
    )
    (net (code "35") (name "/UART3_TX{slash}SCL") (class "Default")
      (node (ref "C12") (pin "1") (pinfunction "1_1") (pintype "passive"))
      (node (ref "R9") (pin "2") (pinfunction "2_2") (pintype "passive"))
      (node (ref "U4") (pin "21") (pinfunction "PB10/I2C2_SCL/USART3_TX/TIM2_CH3_21") (pintype "bidirectional"))
    )
    (net (code "36") (name "/UART_RX") (class "Default")
      (node (ref "C10") (pin "3") (pinfunction "3_3") (pintype "passive"))
      (node (ref "R38") (pin "1") (pinfunction "1_1") (pintype "passive"))
      (node (ref "SB1") (pin "1") (pintype "passive"))
      (node (ref "U1") (pin "4") (pinfunction "2Y_4") (pintype "passive"))
    )
    (net (code "37") (name "/UART_TX") (class "Default")
      (node (ref "C10") (pin "2") (pinfunction "2_2") (pintype "passive"))
      (node (ref "R2") (pin "2") (pinfunction "2_2") (pintype "passive"))
      (node (ref "R37") (pin "1") (pinfunction "1_1") (pintype "passive"))
      (node (ref "SB3") (pin "1") (pintype "passive"))
      (node (ref "U1") (pin "5") (pinfunction "3A_5") (pintype "passive"))
    )
    (net (code "38") (name "5VDC") (class "Default")
      (node (ref "C1") (pin "2") (pinfunction "2_2") (pintype "passive"))
      (node (ref "C10") (pin "5") (pinfunction "5_5") (pintype "passive"))
      (node (ref "C11") (pin "2") (pinfunction "2_2") (pintype "passive"))
      (node (ref "C11") (pin "9") (pinfunction "9_9") (pintype "passive"))
      (node (ref "C12") (pin "5") (pinfunction "5_5") (pintype "passive"))
      (node (ref "C14") (pin "1") (pinfunction "1_1") (pintype "passive"))
      (node (ref "C18") (pin "1") (pinfunction "1_1") (pintype "passive"))
      (node (ref "C19") (pin "1") (pinfunction "1_1") (pintype "passive"))
      (node (ref "C2") (pin "1") (pinfunction "1_1") (pintype "passive"))
      (node (ref "C22") (pin "10") (pinfunction "10_10") (pintype "passive"))
      (node (ref "C5") (pin "2") (pinfunction "2_2") (pintype "passive"))
      (node (ref "C9") (pin "1") (pinfunction "1_1") (pintype "passive"))
      (node (ref "D4") (pin "2") (pinfunction "2_2") (pintype "passive"))
      (node (ref "IC1") (pin "8") (pinfunction "VCC_8") (pintype "passive"))
      (node (ref "LCD1") (pin "15") (pinfunction "A_15") (pintype "passive"))
      (node (ref "LCD1") (pin "2") (pinfunction "VDD_2") (pintype "passive"))
      (node (ref "R3") (pin "2") (pinfunction "2_2") (pintype "passive"))
      (node (ref "SP1") (pin "1") (pinfunction "1_1") (pintype "passive"))
      (node (ref "U1") (pin "14") (pinfunction "VCC_14") (pintype "passive"))
      (node (ref "U2") (pin "3") (pinfunction "OUT_3") (pintype "power_in"))
      (node (ref "U3") (pin "3") (pinfunction "IN_3") (pintype "power_in"))
      (node (ref "VR1") (pin "1") (pinfunction "1_1") (pintype "passive"))
    )
    (net (code "39") (name "12VDC") (class "Default")
      (node (ref "C11") (pin "1") (pinfunction "1_1") (pintype "passive"))
      (node (ref "C11") (pin "10") (pinfunction "10_10") (pintype "passive"))
      (node (ref "C13") (pin "1") (pinfunction "1_1") (pintype "passive"))
      (node (ref "C17") (pin "1") (pinfunction "1_1") (pintype "passive"))
      (node (ref "L1") (pin "1") (pinfunction "1_1") (pintype "passive"))
      (node (ref "TVS4") (pin "2") (pinfunction "2_2") (pintype "passive"))
      (node (ref "U2") (pin "1") (pinfunction "IN_1") (pintype "power_in"))
    )
    (net (code "40") (name "12VIN") (class "Default")
      (node (ref "C4") (pin "4") (pinfunction "4_4") (pintype "passive"))
      (node (ref "C7") (pin "3") (pinfunction "3_3") (pintype "passive"))
      (node (ref "D2") (pin "1") (pinfunction "1_1") (pintype "passive"))
      (node (ref "J1") (pin "4") (pinfunction "4_4") (pintype "passive"))
    )
    (net (code "41") (name "GND") (class "Default")
      (node (ref "C1") (pin "1") (pinfunction "1_1") (pintype "passive"))
      (node (ref "C10") (pin "1") (pinfunction "1_1") (pintype "passive"))
      (node (ref "C11") (pin "4") (pinfunction "4_4") (pintype "passive"))
      (node (ref "C11") (pin "5") (pinfunction "5_5") (pintype "passive"))
      (node (ref "C11") (pin "6") (pinfunction "6_6") (pintype "passive"))
      (node (ref "C11") (pin "7") (pinfunction "7_7") (pintype "passive"))
      (node (ref "C12") (pin "3") (pinfunction "3_3") (pintype "passive"))
      (node (ref "C13") (pin "2") (pinfunction "2_2") (pintype "passive"))
      (node (ref "C14") (pin "2") (pinfunction "2_2") (pintype "passive"))
      (node (ref "C15") (pin "2") (pinfunction "2_2") (pintype "passive"))
      (node (ref "C16") (pin "2") (pinfunction "2_2") (pintype "passive"))
      (node (ref "C17") (pin "2") (pinfunction "2_2") (pintype "passive"))
      (node (ref "C18") (pin "2") (pinfunction "2_2") (pintype "passive"))
      (node (ref "C19") (pin "2") (pinfunction "2_2") (pintype "passive"))
      (node (ref "C2") (pin "2") (pinfunction "2_2") (pintype "passive"))
      (node (ref "C20") (pin "2") (pinfunction "2_2") (pintype "passive"))
      (node (ref "C21") (pin "2") (pinfunction "2_2") (pintype "passive"))
      (node (ref "C22") (pin "8") (pinfunction "8_8") (pintype "passive"))
      (node (ref "C22") (pin "9") (pinfunction "9_9") (pintype "passive"))
      (node (ref "C23") (pin "1") (pinfunction "1_1") (pintype "passive"))
      (node (ref "C24") (pin "1") (pinfunction "1_1") (pintype "passive"))
      (node (ref "C25") (pin "1") (pinfunction "1_1") (pintype "passive"))
      (node (ref "C26") (pin "1") (pinfunction "1_1") (pintype "passive"))
      (node (ref "C27") (pin "1") (pinfunction "1_1") (pintype "passive"))
      (node (ref "C28") (pin "1") (pinfunction "1_1") (pintype "passive"))
      (node (ref "C29") (pin "1") (pinfunction "1_1") (pintype "passive"))
      (node (ref "C3") (pin "1") (pinfunction "1_1") (pintype "passive"))
      (node (ref "C30") (pin "2") (pinfunction "2_2") (pintype "passive"))
      (node (ref "C31") (pin "1") (pinfunction "1_1") (pintype "passive"))
      (node (ref "C32") (pin "2") (pinfunction "2_2") (pintype "passive"))
      (node (ref "C33") (pin "2") (pinfunction "2_2") (pintype "passive"))
      (node (ref "C34") (pin "2") (pinfunction "2_2") (pintype "passive"))
      (node (ref "C35") (pin "2") (pinfunction "2_2") (pintype "passive"))
      (node (ref "C36") (pin "2") (pinfunction "2_2") (pintype "passive"))
      (node (ref "C4") (pin "1") (pinfunction "1_1") (pintype "passive"))
      (node (ref "C6") (pin "1") (pinfunction "1_1") (pintype "passive"))
      (node (ref "C7") (pin "2") (pinfunction "2_2") (pintype "passive"))
      (node (ref "C8") (pin "2") (pinfunction "2_2") (pintype "passive"))
      (node (ref "C9") (pin "2") (pinfunction "2_2") (pintype "passive"))
      (node (ref "D3") (pin "1") (pinfunction "1_1") (pintype "passive"))
      (node (ref "IC1") (pin "5") (pinfunction "GND_5") (pintype "passive"))
      (node (ref "J1") (pin "1") (pinfunction "1_1") (pintype "passive"))
      (node (ref "LCD1") (pin "1") (pinfunction "GND_1") (pintype "passive"))
      (node (ref "LCD1") (pin "16") (pinfunction "K_16") (pintype "passive"))
      (node (ref "Q1") (pin "1") (pinfunction "E_1") (pintype "passive"))
      (node (ref "R10") (pin "2") (pinfunction "2_2") (pintype "passive"))
      (node (ref "R11") (pin "2") (pinfunction "2_2") (pintype "passive"))
      (node (ref "R19") (pin "2") (pinfunction "2_2") (pintype "passive"))
      (node (ref "R24") (pin "1") (pinfunction "1_1") (pintype "passive"))
      (node (ref "R27") (pin "1") (pinfunction "1_1") (pintype "passive"))
      (node (ref "R31") (pin "2") (pinfunction "2_2") (pintype "passive"))
      (node (ref "R40") (pin "2") (pinfunction "2_2") (pintype "passive"))
      (node (ref "R5") (pin "1") (pinfunction "1_1") (pintype "passive"))
      (node (ref "S2") (pin "2") (pinfunction "2_2") (pintype "passive"))
      (node (ref "SW1") (pin "1") (pintype "passive"))
      (node (ref "SW1") (pin "4") (pintype "passive"))
      (node (ref "SW2") (pin "1") (pintype "passive"))
      (node (ref "SW2") (pin "4") (pintype "passive"))
      (node (ref "SW3") (pin "1") (pintype "passive"))
      (node (ref "SW3") (pin "4") (pintype "passive"))
      (node (ref "SW4") (pin "1") (pintype "passive"))
      (node (ref "SW4") (pin "4") (pintype "passive"))
      (node (ref "SW5") (pin "1") (pintype "passive"))
      (node (ref "SW5") (pin "4") (pintype "passive"))
      (node (ref "TVS1") (pin "2") (pinfunction "2_2") (pintype "passive"))
      (node (ref "TVS3") (pin "1") (pinfunction "1_1") (pintype "passive"))
      (node (ref "TVS4") (pin "1") (pinfunction "1_1") (pintype "passive"))
      (node (ref "U1") (pin "7") (pinfunction "GND_7") (pintype "passive"))
      (node (ref "U2") (pin "2") (pinfunction "GND_2") (pintype "power_in"))
      (node (ref "U3") (pin "1") (pinfunction "GND_1") (pintype "power_in"))
      (node (ref "U4") (pin "23") (pinfunction "VSS_1_23") (pintype "power_in"))
      (node (ref "U4") (pin "35") (pinfunction "VSS_2_35") (pintype "power_in"))
      (node (ref "U4") (pin "47") (pinfunction "VSS_3_47") (pintype "power_in"))
      (node (ref "U4") (pin "8") (pinfunction "VSSA_8") (pintype "power_in"))
      (node (ref "VR1") (pin "3") (pinfunction "3_3") (pintype "passive"))
    )
    (net (code "42") (name "Net-(C8-Pad1)") (class "Default")
      (node (ref "C8") (pin "1") (pinfunction "1_1") (pintype "passive"))
      (node (ref "D2") (pin "2") (pinfunction "2_2") (pintype "passive"))
      (node (ref "F3") (pin "2") (pinfunction "2_2") (pintype "passive"))
    )
    (net (code "43") (name "Net-(F3-Pad1)") (class "Default")
      (node (ref "F3") (pin "1") (pinfunction "1_1") (pintype "passive"))
      (node (ref "L1") (pin "2") (pinfunction "2_2") (pintype "passive"))
    )
    (net (code "44") (name "Net-(IC1-A)") (class "Default")
      (node (ref "C6") (pin "2") (pinfunction "2_2") (pintype "passive"))
      (node (ref "F2") (pin "1") (pinfunction "1_1") (pintype "passive"))
      (node (ref "IC1") (pin "6") (pinfunction "A_6") (pintype "passive"))
      (node (ref "R4") (pin "1") (pinfunction "1_1") (pintype "passive"))
      (node (ref "R5") (pin "2") (pinfunction "2_2") (pintype "passive"))
      (node (ref "TVS2") (pin "1") (pinfunction "1_1") (pintype "passive"))
      (node (ref "TVS3") (pin "2") (pinfunction "2_2") (pintype "passive"))
    )
    (net (code "45") (name "Net-(IC1-B)") (class "Default")
      (node (ref "C5") (pin "1") (pinfunction "1_1") (pintype "passive"))
      (node (ref "F1") (pin "1") (pinfunction "1_1") (pintype "passive"))
      (node (ref "IC1") (pin "7") (pinfunction "B_7") (pintype "passive"))
      (node (ref "R3") (pin "1") (pinfunction "1_1") (pintype "passive"))
      (node (ref "R4") (pin "2") (pinfunction "2_2") (pintype "passive"))
      (node (ref "TVS1") (pin "1") (pinfunction "1_1") (pintype "passive"))
      (node (ref "TVS2") (pin "2") (pinfunction "2_2") (pintype "passive"))
    )
    (net (code "46") (name "Net-(IC1-DE)") (class "Default")
      (node (ref "IC1") (pin "2") (pinfunction "~{RE}_2") (pintype "passive"))
      (node (ref "IC1") (pin "3") (pinfunction "DE_3") (pintype "passive"))
      (node (ref "SB2") (pin "2") (pintype "passive"))
      (node (ref "U1") (pin "10") (pinfunction "5Y_10") (pintype "passive"))
    )
    (net (code "47") (name "Net-(IC1-DI)") (class "Default")
      (node (ref "D1") (pin "2") (pinfunction "2_2") (pintype "passive"))
      (node (ref "IC1") (pin "4") (pinfunction "DI_4") (pintype "passive"))
      (node (ref "R1") (pin "1") (pinfunction "1_1") (pintype "passive"))
      (node (ref "SB3") (pin "2") (pintype "passive"))
      (node (ref "U1") (pin "8") (pinfunction "4Y_8") (pintype "passive"))
    )
    (net (code "48") (name "Net-(IC1-RO)") (class "Default")
      (node (ref "IC1") (pin "1") (pinfunction "RO_1") (pintype "passive"))
      (node (ref "SB1") (pin "2") (pintype "passive"))
      (node (ref "U1") (pin "13") (pinfunction "6A_13") (pintype "passive"))
    )
    (net (code "49") (name "Net-(LCD1-VEE)") (class "Default")
      (node (ref "LCD1") (pin "3") (pinfunction "VEE_3") (pintype "passive"))
      (node (ref "VR1") (pin "2") (pinfunction "2_2") (pintype "passive"))
    )
    (net (code "50") (name "Net-(LED1-Pad2)") (class "Default")
      (node (ref "LED1") (pin "2") (pinfunction "2_2") (pintype "passive"))
      (node (ref "R10") (pin "1") (pinfunction "1_1") (pintype "passive"))
    )
    (net (code "51") (name "Net-(LED2-Pad2)") (class "Default")
      (node (ref "LED2") (pin "2") (pinfunction "2_2") (pintype "passive"))
      (node (ref "R11") (pin "1") (pinfunction "1_1") (pintype "passive"))
    )
    (net (code "52") (name "Net-(LED3-Pad2)") (class "Default")
      (node (ref "LED3") (pin "2") (pinfunction "2_2") (pintype "passive"))
      (node (ref "R12") (pin "1") (pinfunction "1_1") (pintype "passive"))
    )
    (net (code "53") (name "Net-(LED4-Pad2)") (class "Default")
      (node (ref "LED4") (pin "2") (pinfunction "2_2") (pintype "passive"))
      (node (ref "R13") (pin "1") (pinfunction "1_1") (pintype "passive"))
    )
    (net (code "54") (name "Net-(LED5-Pad2)") (class "Default")
      (node (ref "LED5") (pin "2") (pinfunction "2_2") (pintype "passive"))
      (node (ref "R14") (pin "1") (pinfunction "1_1") (pintype "passive"))
    )
    (net (code "55") (name "Net-(LED6-Pad2)") (class "Default")
      (node (ref "LED6") (pin "2") (pinfunction "2_2") (pintype "passive"))
      (node (ref "R15") (pin "1") (pinfunction "1_1") (pintype "passive"))
    )
    (net (code "56") (name "Net-(LED7-Pad2)") (class "Default")
      (node (ref "LED7") (pin "2") (pinfunction "2_2") (pintype "passive"))
      (node (ref "R16") (pin "1") (pinfunction "1_1") (pintype "passive"))
    )
    (net (code "57") (name "Net-(LED8-Pad2)") (class "Default")
      (node (ref "LED8") (pin "2") (pinfunction "2_2") (pintype "passive"))
      (node (ref "R17") (pin "1") (pinfunction "1_1") (pintype "passive"))
    )
    (net (code "58") (name "Net-(LED9-Pad2)") (class "Default")
      (node (ref "LED9") (pin "2") (pinfunction "2_2") (pintype "passive"))
      (node (ref "R18") (pin "1") (pinfunction "1_1") (pintype "passive"))
    )
    (net (code "59") (name "Net-(LED10-Pad2)") (class "Default")
      (node (ref "LED10") (pin "2") (pinfunction "2_2") (pintype "passive"))
      (node (ref "R19") (pin "1") (pinfunction "1_1") (pintype "passive"))
    )
    (net (code "60") (name "Net-(Q1-B)") (class "Default")
      (node (ref "Q1") (pin "2") (pinfunction "B_2") (pintype "passive"))
      (node (ref "R25") (pin "2") (pinfunction "2_2") (pintype "passive"))
    )
    (net (code "61") (name "Net-(Q1-C)") (class "Default")
      (node (ref "D4") (pin "1") (pinfunction "1_1") (pintype "passive"))
      (node (ref "Q1") (pin "3") (pinfunction "C_3") (pintype "passive"))
      (node (ref "SP1") (pin "2") (pinfunction "2_2") (pintype "passive"))
    )
    (net (code "62") (name "Net-(R20-Pad1)") (class "Default")
      (node (ref "R20") (pin "1") (pinfunction "1_1") (pintype "passive"))
      (node (ref "S1") (pin "1") (pinfunction "1_1") (pintype "passive"))
    )
    (net (code "63") (name "Net-(R21-Pad1)") (class "Default")
      (node (ref "R21") (pin "1") (pinfunction "1_1") (pintype "passive"))
      (node (ref "S1") (pin "2") (pinfunction "2_2") (pintype "passive"))
    )
    (net (code "64") (name "Net-(R22-Pad1)") (class "Default")
      (node (ref "R22") (pin "1") (pinfunction "1_1") (pintype "passive"))
      (node (ref "S1") (pin "3") (pinfunction "3_3") (pintype "passive"))
    )
    (net (code "65") (name "Net-(R23-Pad1)") (class "Default")
      (node (ref "R23") (pin "1") (pinfunction "1_1") (pintype "passive"))
      (node (ref "S1") (pin "4") (pinfunction "4_4") (pintype "passive"))
    )
    (net (code "66") (name "Net-(R26-Pad1)") (class "Default")
      (node (ref "R26") (pin "1") (pinfunction "1_1") (pintype "passive"))
      (node (ref "S1") (pin "5") (pinfunction "5_5") (pintype "passive"))
    )
    (net (code "67") (name "Net-(R28-Pad1)") (class "Default")
      (node (ref "R28") (pin "1") (pinfunction "1_1") (pintype "passive"))
      (node (ref "S1") (pin "6") (pinfunction "6_6") (pintype "passive"))
    )
    (net (code "68") (name "Net-(R29-Pad1)") (class "Default")
      (node (ref "R29") (pin "1") (pinfunction "1_1") (pintype "passive"))
      (node (ref "S1") (pin "7") (pinfunction "7_7") (pintype "passive"))
    )
    (net (code "69") (name "Net-(R30-Pad1)") (class "Default")
      (node (ref "R30") (pin "1") (pinfunction "1_1") (pintype "passive"))
      (node (ref "S1") (pin "8") (pinfunction "8_8") (pintype "passive"))
    )
    (net (code "70") (name "Net-(U1-5A)") (class "Default")
      (node (ref "C3") (pin "2") (pinfunction "2_2") (pintype "passive"))
      (node (ref "D1") (pin "1") (pinfunction "1_1") (pintype "passive"))
      (node (ref "R1") (pin "2") (pinfunction "2_2") (pintype "passive"))
      (node (ref "U1") (pin "11") (pinfunction "5A_11") (pintype "passive"))
    )
    (net (code "71") (name "Net-(U4A-BOOT0)") (class "Default")
      (node (ref "R40") (pin "1") (pinfunction "1_1") (pintype "passive"))
      (node (ref "U4") (pin "44") (pinfunction "BOOT0_44") (pintype "input"))
    )
    (net (code "72") (name "Net-(U4A-PA9{slash}USART1_TX{slash}TIM1_CH2)") (class "Default")
      (node (ref "R37") (pin "2") (pinfunction "2_2") (pintype "passive"))
      (node (ref "U4") (pin "30") (pinfunction "PA9/USART1_TX/TIM1_CH2_30") (pintype "bidirectional"))
    )
    (net (code "73") (name "Net-(U4A-PA10{slash}USART1_RX{slash}TIM1_CH3)") (class "Default")
      (node (ref "R38") (pin "2") (pinfunction "2_2") (pintype "passive"))
      (node (ref "U4") (pin "31") (pinfunction "PA10/USART1_RX/TIM1_CH3_31") (pintype "bidirectional"))
    )
    (net (code "74") (name "Net-(U4A-PB2{slash}BOOT1)") (class "Default")
      (node (ref "R31") (pin "1") (pinfunction "1_1") (pintype "passive"))
      (node (ref "U4") (pin "20") (pinfunction "PB2/BOOT1_20") (pintype "bidirectional"))
    )
    (net (code "75") (name "Net-(U4A-PD0-OSC_IN)") (class "Default")
      (node (ref "C30") (pin "1") (pinfunction "1_1") (pintype "passive"))
      (node (ref "U4") (pin "5") (pinfunction "PD0-OSC_IN_5") (pintype "bidirectional"))
      (node (ref "X1") (pin "1") (pinfunction "1_1") (pintype "passive"))
    )
    (net (code "76") (name "Net-(U4A-PD1-OSC_OUT)") (class "Default")
      (node (ref "C32") (pin "1") (pinfunction "1_1") (pintype "passive"))
      (node (ref "U4") (pin "6") (pinfunction "PD1-OSC_OUT_6") (pintype "bidirectional"))
      (node (ref "X1") (pin "2") (pinfunction "2_2") (pintype "passive"))
    )
    (net (code "77") (name "unconnected-(C7-Pad1)") (class "Default")
      (node (ref "C7") (pin "1") (pinfunction "1_1") (pintype "passive"))
    )
    (net (code "78") (name "unconnected-(C12-Pad6)") (class "Default")
      (node (ref "C12") (pin "6") (pinfunction "6_6") (pintype "passive"))
    )
    (net (code "79") (name "unconnected-(LCD1-D0-Pad7)") (class "Default")
      (node (ref "LCD1") (pin "7") (pinfunction "D0_7") (pintype "passive"))
    )
    (net (code "80") (name "unconnected-(LCD1-D1-Pad8)") (class "Default")
      (node (ref "LCD1") (pin "8") (pinfunction "D1_8") (pintype "passive"))
    )
    (net (code "81") (name "unconnected-(LCD1-D2-Pad9)") (class "Default")
      (node (ref "LCD1") (pin "9") (pinfunction "D2_9") (pintype "passive"))
    )
    (net (code "82") (name "unconnected-(LCD1-D3-Pad10)") (class "Default")
      (node (ref "LCD1") (pin "10") (pinfunction "D3_10") (pintype "passive"))
    )
    (net (code "83") (name "unconnected-(U1-1A-Pad1)") (class "Default")
      (node (ref "U1") (pin "1") (pinfunction "1A_1") (pintype "passive"))
    )
    (net (code "84") (name "unconnected-(U1-1Y-Pad2)") (class "Default")
      (node (ref "U1") (pin "2") (pinfunction "1Y_2") (pintype "passive"))
    )
    (net (code "85") (name "unconnected-(U4A-PA11{slash}USART1_CTS{slash}CANRX{slash}USBDM{slash}TIM1_CH4-Pad32)") (class "Default")
      (node (ref "U4") (pin "32") (pinfunction "PA11/USART1_CTS/CANRX/USBDM/TIM1_CH4_32") (pintype "bidirectional"))
    )
    (net (code "86") (name "unconnected-(U4A-PA12{slash}USART1_RTS{slash}CANTX{slash}USBDP{slash}TIM1_ETR-Pad33)") (class "Default")
      (node (ref "U4") (pin "33") (pinfunction "PA12/USART1_RTS/CANTX/USBDP/TIM1_ETR_33") (pintype "bidirectional"))
    )
    (net (code "87") (name "unconnected-(U4A-PA15{slash}JTDI{slash}TIM2_CH1_ETR{slash}SPI1_NSS-Pad38)") (class "Default")
      (node (ref "U4") (pin "38") (pinfunction "PA15/JTDI/TIM2_CH1_ETR/SPI1_NSS_38") (pintype "bidirectional"))
    )
  )
)
